# 02_Amplier.net
KiCad netlist of a schematic drawn in Altium Designer
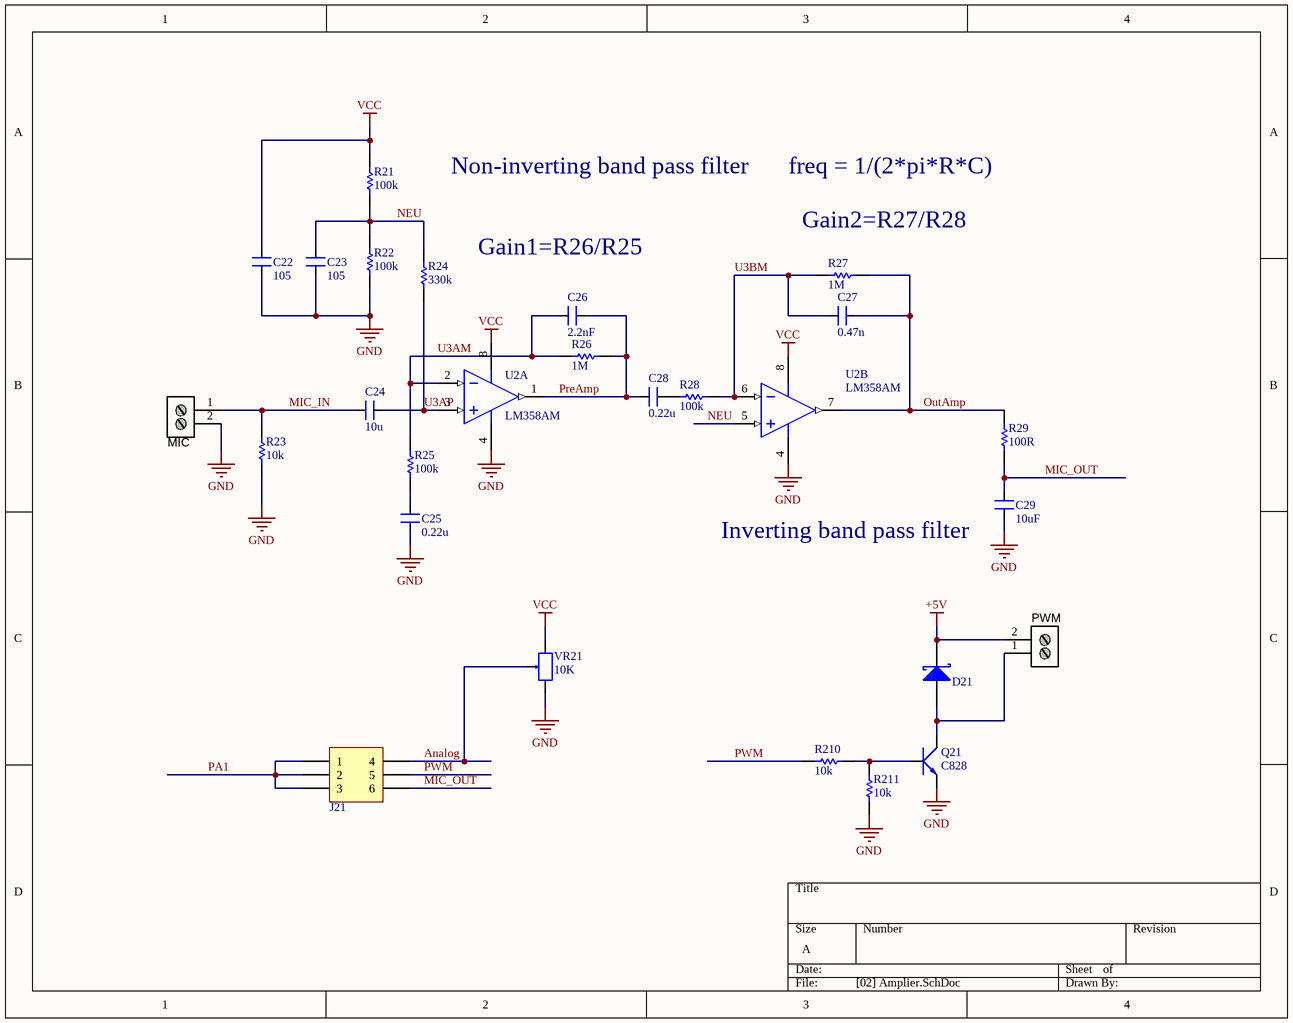
[diagram p0: [02] Amplier.SchDoc]

(export (version "E")
  (design (tool "Eeschema 10.0.6"))
  (components
    (comp (ref "C22")
      (value "105")
      (footprint "CAPC2012N_F")
      (fields (field (name "Comment") "CAP NP"))
      (libsource (lib "Tuan") (part "CAP NP"))
    )
    (comp (ref "C23")
      (value "105")
      (footprint "CAPC2012N_F")
      (fields (field (name "Comment") "CAP NP"))
      (libsource (lib "Tuan") (part "CAP NP"))
    )
    (comp (ref "C24")
      (value "10u")
      (footprint "CAPC2012N_F")
      (fields (field (name "Comment") "CAP NP"))
      (libsource (lib "Tuan") (part "CAP NP"))
    )
    (comp (ref "C25")
      (value "0.22u")
      (footprint "CAPC2012N_F")
      (fields (field (name "Comment") "CAP NP"))
      (libsource (lib "Tuan") (part "CAP NP"))
    )
    (comp (ref "C26")
      (value "2.2nF")
      (footprint "CAPC2012N_F")
      (fields (field (name "Comment") "CAP NP"))
      (libsource (lib "Tuan") (part "CAP NP"))
    )
    (comp (ref "C27")
      (value "0.47n")
      (footprint "CAPC2012N_F")
      (fields (field (name "Comment") "CAP NP"))
      (libsource (lib "Tuan") (part "CAP NP"))
    )
    (comp (ref "C28")
      (value "0.22u")
      (footprint "CAPC2012N_F")
      (fields (field (name "Comment") "CAP NP"))
      (libsource (lib "Tuan") (part "CAP NP"))
    )
    (comp (ref "C29")
      (value "10uF")
      (footprint "CAPC2012N_F")
      (fields (field (name "Comment") "CAP NP"))
      (libsource (lib "Tuan") (part "CAP NP"))
    )
    (comp (ref "D21") (value "Diode") (footprint "DO-214AC") (libsource (lib "Tuan") (part "Diode")))
    (comp (ref "J21")
      (value "Header 3X2A")
      (footprint "heromap:HDR2X3_CEN")
      (description "Header, 3-Pin, Dual row")
      (fields (field (name "PUBLISHER") "Altium Limited"))
      (libsource (lib "heromap") (part "Header 3X2A"))
    )
    (comp (ref "MIC")
      (value "Stackable ScrewTerm")
      (footprint "2P_PCB_ScrewTerm_200mil")
      (description "Terminal Block Screw Type THT 2-Position 3.81mm pitch")
      (libsource (lib "") (part "2P_ScrewTerm_90S_3.81MM_1"))
    )
    (comp (ref "PWM")
      (value "Stackable ScrewTerm")
      (footprint "2P_PCB_ScrewTerm_200mil")
      (description "Terminal Block Screw Type THT 2-Position 3.81mm pitch")
      (libsource (lib "PBL - Connectors") (part "2P_ScrewTerm_90S_3.81MM"))
    )
    (comp (ref "Q21")
      (value "C828")
      (footprint "SOT23 TOP")
      (description "Transistor C828 C1815....")
      (libsource (lib "Tuan") (part "NPN"))
    )
    (comp (ref "R21")
      (value "100k")
      (footprint "RESC2012N_F")
      (fields (field (name "Comment") "Res"))
      (libsource (lib "Tuan") (part "Res"))
    )
    (comp (ref "R22")
      (value "100k")
      (footprint "RESC2012N_F")
      (fields (field (name "Comment") "Res"))
      (libsource (lib "Tuan") (part "Res"))
    )
    (comp (ref "R23")
      (value "10k")
      (footprint "RESC2012N_F")
      (fields (field (name "Comment") "Res"))
      (libsource (lib "Tuan") (part "Res"))
    )
    (comp (ref "R24")
      (value "330k")
      (footprint "RESC2012N_F")
      (fields (field (name "Comment") "Res"))
      (libsource (lib "Tuan") (part "Res"))
    )
    (comp (ref "R25")
      (value "100k")
      (footprint "RESC2012N_F")
      (fields (field (name "Comment") "Res"))
      (libsource (lib "Tuan") (part "Res"))
    )
    (comp (ref "R26")
      (value "1M")
      (footprint "RESC2012N_F")
      (fields (field (name "Comment") "Res"))
      (libsource (lib "Tuan") (part "Res"))
    )
    (comp (ref "R27")
      (value "1M")
      (footprint "RESC2012N_F")
      (fields (field (name "Comment") "Res"))
      (libsource (lib "Tuan") (part "Res"))
    )
    (comp (ref "R28")
      (value "100k")
      (footprint "RESC2012N_F")
      (fields (field (name "Comment") "Res"))
      (libsource (lib "Tuan") (part "Res"))
    )
    (comp (ref "R29")
      (value "100R")
      (footprint "RESC2012N_F")
      (fields (field (name "Comment") "Res"))
      (libsource (lib "Tuan") (part "Res"))
    )
    (comp (ref "R210")
      (value "10k")
      (footprint "RESC1608N_ZERO")
      (fields (field (name "Comment") "Res"))
      (libsource (lib "Tuan") (part "Res"))
    )
    (comp (ref "R211")
      (value "10k")
      (footprint "RESC1608N_ZERO")
      (fields (field (name "Comment") "Res"))
      (libsource (lib "Tuan") (part "Res"))
    )
    (comp (ref "U2")
      (value "LM358AM")
      (footprint "M08A_N")
      (description "Low Power Dual Operational Amplifier")
      (fields
        (field (name "MANUFACTURER") "National Semiconductor")
        (field (name "DIGIKEYPARTNUMBER") "LM358AMXCT-ND")
        (field (name "PUBLISHER") "Altium Limited")
      )
      (libsource (lib "NSC Amplifier") (part "LM358AM"))
    )
    (comp (ref "VR21")
      (value "10K")
      (footprint "VR1")
      (description "Var Resistor")
      (libsource (lib "syhaunguyen") (part "VR"))
    )
  )
  (nets
    (net (code "1") (name "+5V") (class "Default")
      (node (ref "D21") (pin "2") (pinfunction "K_2") (pintype "passive"))
      (node (ref "PWM") (pin "2") (pinfunction "2_2") (pintype "passive"))
    )
    (net (code "2") (name "/Analog") (class "Default")
      (node (ref "J21") (pin "4") (pinfunction "4_4") (pintype "passive"))
      (node (ref "VR21") (pin "2") (pinfunction "2_2") (pintype "passive"))
    )
    (net (code "3") (name "/MIC_IN") (class "Default")
      (node (ref "C24") (pin "2") (pinfunction "2_2") (pintype "passive"))
      (node (ref "MIC") (pin "1") (pinfunction "1_1") (pintype "passive"))
      (node (ref "R23") (pin "1") (pinfunction "1_1") (pintype "passive"))
    )
    (net (code "4") (name "/MIC_OUT") (class "Default")
      (node (ref "C29") (pin "1") (pinfunction "1_1") (pintype "passive"))
      (node (ref "J21") (pin "6") (pinfunction "6_6") (pintype "passive"))
      (node (ref "R29") (pin "1") (pinfunction "1_1") (pintype "passive"))
    )
    (net (code "5") (name "/NEU") (class "Default")
      (node (ref "C23") (pin "2") (pinfunction "2_2") (pintype "passive"))
      (node (ref "R21") (pin "1") (pinfunction "1_1") (pintype "passive"))
      (node (ref "R22") (pin "2") (pinfunction "2_2") (pintype "passive"))
      (node (ref "R24") (pin "1") (pinfunction "1_1") (pintype "passive"))
      (node (ref "U2") (pin "5") (pinfunction "INB+_5") (pintype "input"))
    )
    (net (code "6") (name "/OutAmp") (class "Default")
      (node (ref "C27") (pin "1") (pinfunction "1_1") (pintype "passive"))
      (node (ref "R27") (pin "1") (pinfunction "1_1") (pintype "passive"))
      (node (ref "R29") (pin "2") (pinfunction "2_2") (pintype "passive"))
      (node (ref "U2") (pin "7") (pinfunction "OUTB_7") (pintype "output"))
    )
    (net (code "7") (name "/PA1") (class "Default")
      (node (ref "J21") (pin "1") (pinfunction "1_1") (pintype "passive"))
      (node (ref "J21") (pin "2") (pinfunction "2_2") (pintype "passive"))
      (node (ref "J21") (pin "3") (pinfunction "3_3") (pintype "passive"))
    )
    (net (code "8") (name "/PWM") (class "Default")
      (node (ref "J21") (pin "5") (pinfunction "5_5") (pintype "passive"))
      (node (ref "R210") (pin "1") (pinfunction "1_1") (pintype "passive"))
    )
    (net (code "9") (name "/PreAmp") (class "Default")
      (node (ref "C26") (pin "1") (pinfunction "1_1") (pintype "passive"))
      (node (ref "C28") (pin "2") (pinfunction "2_2") (pintype "passive"))
      (node (ref "R26") (pin "1") (pinfunction "1_1") (pintype "passive"))
      (node (ref "U2") (pin "1") (pinfunction "OUTA_1") (pintype "output"))
    )
    (net (code "10") (name "/U3AM") (class "Default")
      (node (ref "C26") (pin "2") (pinfunction "2_2") (pintype "passive"))
      (node (ref "R25") (pin "1") (pinfunction "1_1") (pintype "passive"))
      (node (ref "R26") (pin "2") (pinfunction "2_2") (pintype "passive"))
      (node (ref "U2") (pin "2") (pinfunction "INA-_2") (pintype "input"))
    )
    (net (code "11") (name "/U3AP") (class "Default")
      (node (ref "C24") (pin "1") (pinfunction "1_1") (pintype "passive"))
      (node (ref "R24") (pin "2") (pinfunction "2_2") (pintype "passive"))
      (node (ref "U2") (pin "3") (pinfunction "INA+_3") (pintype "input"))
    )
    (net (code "12") (name "/U3BM") (class "Default")
      (node (ref "C27") (pin "2") (pinfunction "2_2") (pintype "passive"))
      (node (ref "R27") (pin "2") (pinfunction "2_2") (pintype "passive"))
      (node (ref "R28") (pin "2") (pinfunction "2_2") (pintype "passive"))
      (node (ref "U2") (pin "6") (pinfunction "INB-_6") (pintype "input"))
    )
    (net (code "13") (name "GND") (class "Default")
      (node (ref "C22") (pin "1") (pinfunction "1_1") (pintype "passive"))
      (node (ref "C23") (pin "1") (pinfunction "1_1") (pintype "passive"))
      (node (ref "C25") (pin "1") (pinfunction "1_1") (pintype "passive"))
      (node (ref "C29") (pin "2") (pinfunction "2_2") (pintype "passive"))
      (node (ref "MIC") (pin "2") (pinfunction "2_2") (pintype "passive"))
      (node (ref "Q21") (pin "3") (pinfunction "E_3") (pintype "passive"))
      (node (ref "R211") (pin "1") (pinfunction "1_1") (pintype "passive"))
      (node (ref "R22") (pin "1") (pinfunction "1_1") (pintype "passive"))
      (node (ref "R23") (pin "2") (pinfunction "2_2") (pintype "passive"))
      (node (ref "U2") (pin "4") (pinfunction "GND_4") (pintype "power_in"))
      (node (ref "VR21") (pin "1") (pinfunction "1_1") (pintype "passive"))
    )
    (net (code "14") (name "Net-(C25-Pad2)") (class "Default")
      (node (ref "C25") (pin "2") (pinfunction "2_2") (pintype "passive"))
      (node (ref "R25") (pin "2") (pinfunction "2_2") (pintype "passive"))
    )
    (net (code "15") (name "Net-(C28-Pad1)") (class "Default")
      (node (ref "C28") (pin "1") (pinfunction "1_1") (pintype "passive"))
      (node (ref "R28") (pin "1") (pinfunction "1_1") (pintype "passive"))
    )
    (net (code "16") (name "Net-(D21-A)") (class "Default")
      (node (ref "D21") (pin "1") (pinfunction "A_1") (pintype "passive"))
      (node (ref "PWM") (pin "1") (pinfunction "1_1") (pintype "passive"))
      (node (ref "Q21") (pin "2") (pinfunction "C_2") (pintype "passive"))
    )
    (net (code "17") (name "Net-(Q21-B)") (class "Default")
      (node (ref "Q21") (pin "1") (pinfunction "B_1") (pintype "passive"))
      (node (ref "R210") (pin "2") (pinfunction "2_2") (pintype "passive"))
      (node (ref "R211") (pin "2") (pinfunction "2_2") (pintype "passive"))
    )
    (net (code "18") (name "VCC") (class "Default")
      (node (ref "C22") (pin "2") (pinfunction "2_2") (pintype "passive"))
      (node (ref "R21") (pin "2") (pinfunction "2_2") (pintype "passive"))
      (node (ref "U2") (pin "8") (pinfunction "V+_8") (pintype "power_in"))
      (node (ref "VR21") (pin "3") (pinfunction "3_3") (pintype "passive"))
    )
  )
)
